# Universal_RGB_to_YPbPR.net
KiCad netlist of a schematic drawn in EAGLE
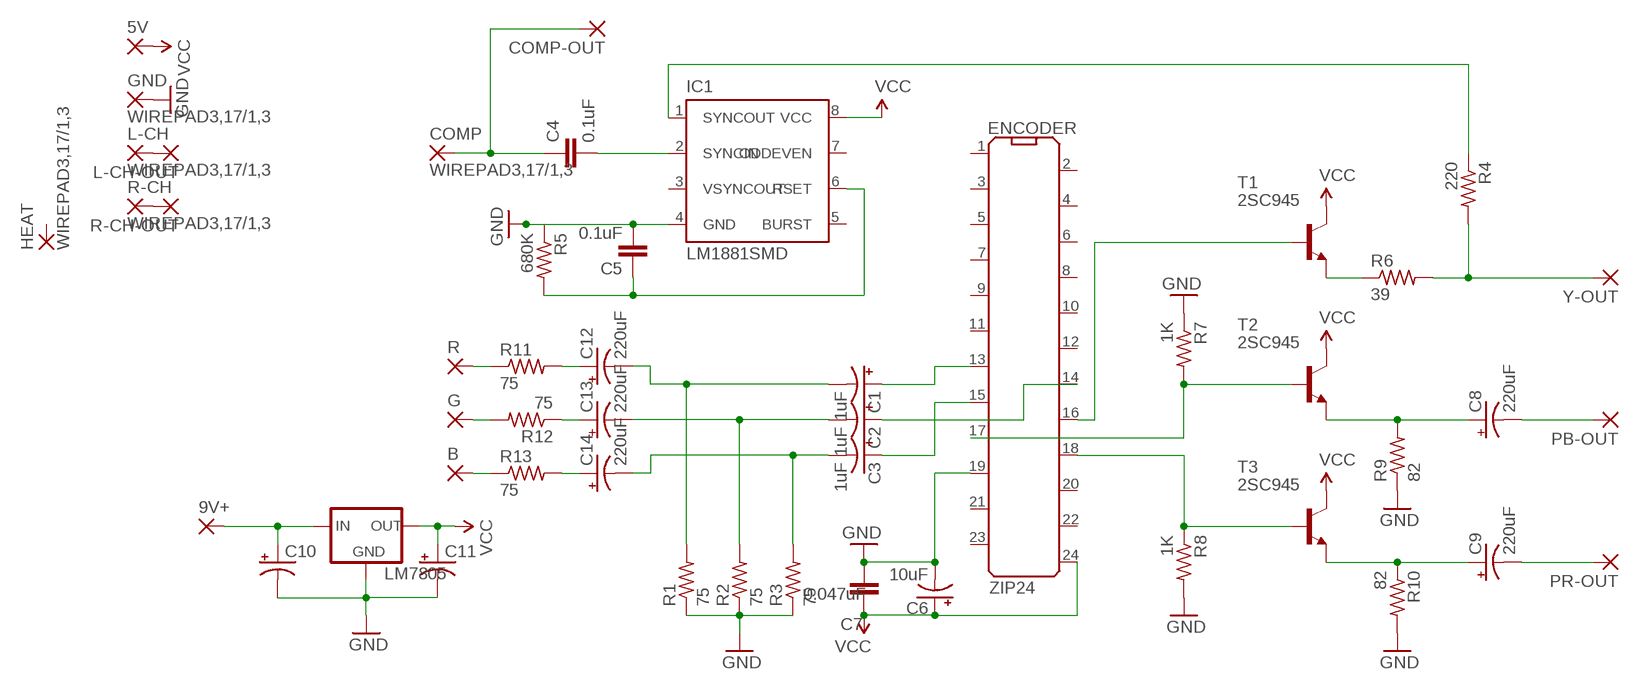
[diagram p0: schematic, sheet 1]

(export (version "E")
  (design (tool "Eeschema 10.0.6"))
  (components
    (comp (ref "5V")
      (value "WIREPAD3,17/1,3")
      (footprint "eagle-import:3,17_1,3")
      (libsource (lib "eagle-import") (part "WIREPAD3,17/1,3"))
    )
    (comp (ref "9V+")
      (value "WIREPAD3,17/1,3")
      (footprint "eagle-import:3,17_1,3")
      (libsource (lib "eagle-import") (part "WIREPAD3,17/1,3"))
    )
    (comp (ref "B")
      (value "WIREPAD3,17/1,3")
      (footprint "eagle-import:3,17_1,3")
      (libsource (lib "eagle-import") (part "WIREPAD3,17/1,3"))
    )
    (comp (ref "C1")
      (value "1uF")
      (footprint "eagle-import:CPOL-RADIAL-10UF-25V")
      (libsource (lib "eagle-import") (part "CAP_POLPTH2"))
    )
    (comp (ref "C2")
      (value "1uF")
      (footprint "eagle-import:CPOL-RADIAL-10UF-25V")
      (libsource (lib "eagle-import") (part "CAP_POLPTH2"))
    )
    (comp (ref "C3")
      (value "1uF")
      (footprint "eagle-import:CPOL-RADIAL-10UF-25V")
      (libsource (lib "eagle-import") (part "CAP_POLPTH2"))
    )
    (comp (ref "C4")
      (value "0.1uF")
      (footprint "eagle-import:C025-024X044")
      (libsource (lib "eagle-import") (part "C-EU025-024X044"))
    )
    (comp (ref "C5")
      (value "0.1uF")
      (footprint "eagle-import:C025-024X044")
      (libsource (lib "eagle-import") (part "C-EU025-024X044"))
    )
    (comp (ref "C6")
      (value "10uF")
      (footprint "eagle-import:CPOL-RADIAL-10UF-25V")
      (libsource (lib "eagle-import") (part "CAP_POLPTH2"))
    )
    (comp (ref "C7")
      (value "0.047uF")
      (footprint "eagle-import:C025-024X044")
      (libsource (lib "eagle-import") (part "C-EU025-024X044"))
    )
    (comp (ref "C8")
      (value "220uF")
      (footprint "eagle-import:CPOL-RADIAL-1000UF-25V")
      (libsource (lib "eagle-import") (part "CAP_POLPTH4"))
    )
    (comp (ref "C9")
      (value "220uF")
      (footprint "eagle-import:CPOL-RADIAL-1000UF-25V")
      (libsource (lib "eagle-import") (part "CAP_POLPTH4"))
    )
    (comp (ref "C10")
      (value "CAP_POLPTH1")
      (footprint "eagle-import:CPOL-RADIAL-100UF-25V")
      (libsource (lib "eagle-import") (part "CAP_POLPTH1"))
    )
    (comp (ref "C11")
      (value "CAP_POLPTH1")
      (footprint "eagle-import:CPOL-RADIAL-100UF-25V")
      (libsource (lib "eagle-import") (part "CAP_POLPTH1"))
    )
    (comp (ref "C12")
      (value "220uF")
      (footprint "eagle-import:CPOL-RADIAL-1000UF-25V")
      (libsource (lib "eagle-import") (part "CAP_POLPTH4"))
    )
    (comp (ref "C13")
      (value "220uF")
      (footprint "eagle-import:CPOL-RADIAL-1000UF-25V")
      (libsource (lib "eagle-import") (part "CAP_POLPTH4"))
    )
    (comp (ref "C14")
      (value "220uF")
      (footprint "eagle-import:CPOL-RADIAL-1000UF-25V")
      (libsource (lib "eagle-import") (part "CAP_POLPTH4"))
    )
    (comp (ref "COMP")
      (value "WIREPAD3,17/1,3")
      (footprint "eagle-import:3,17_1,3")
      (libsource (lib "eagle-import") (part "WIREPAD3,17/1,3"))
    )
    (comp (ref "COMP-OUT")
      (value "WIREPAD3,17/1,3")
      (footprint "eagle-import:3,17_1,3")
      (libsource (lib "eagle-import") (part "WIREPAD3,17/1,3"))
    )
    (comp (ref "ENCODER")
      (value "ZIP24")
      (footprint "eagle-import:ZIP24")
      (libsource (lib "eagle-import") (part "ZIP24"))
    )
    (comp (ref "G")
      (value "WIREPAD3,17/1,3")
      (footprint "eagle-import:3,17_1,3")
      (libsource (lib "eagle-import") (part "WIREPAD3,17/1,3"))
    )
    (comp (ref "GND")
      (value "WIREPAD3,17/1,3")
      (footprint "eagle-import:3,17_1,3")
      (libsource (lib "eagle-import") (part "WIREPAD3,17/1,3"))
    )
    (comp (ref "HEAT")
      (value "WIREPAD3,17/1,3")
      (footprint "eagle-import:3,17_1,3")
      (libsource (lib "eagle-import") (part "WIREPAD3,17/1,3"))
    )
    (comp (ref "IC1")
      (value "LM1881SMD")
      (footprint "eagle-import:SO08")
      (libsource (lib "eagle-import") (part "LM1881SMD"))
    )
    (comp (ref "L-CH")
      (value "WIREPAD3,17/1,3")
      (footprint "eagle-import:3,17_1,3")
      (libsource (lib "eagle-import") (part "WIREPAD3,17/1,3"))
    )
    (comp (ref "L-CH-OUT")
      (value "WIREPAD3,17/1,3")
      (footprint "eagle-import:3,17_1,3")
      (libsource (lib "eagle-import") (part "WIREPAD3,17/1,3"))
    )
    (comp (ref "LM7805")
      (value "V_REG_78XX")
      (footprint "eagle-import:DPAK")
      (libsource (lib "eagle-import") (part "V_REG_78XX"))
    )
    (comp (ref "PB-OUT")
      (value "WIREPAD3,17/1,3")
      (footprint "eagle-import:3,17_1,3")
      (libsource (lib "eagle-import") (part "WIREPAD3,17/1,3"))
    )
    (comp (ref "PR-OUT")
      (value "WIREPAD3,17/1,3")
      (footprint "eagle-import:3,17_1,3")
      (libsource (lib "eagle-import") (part "WIREPAD3,17/1,3"))
    )
    (comp (ref "R")
      (value "WIREPAD3,17/1,3")
      (footprint "eagle-import:3,17_1,3")
      (libsource (lib "eagle-import") (part "WIREPAD3,17/1,3"))
    )
    (comp (ref "R-CH")
      (value "WIREPAD3,17/1,3")
      (footprint "eagle-import:3,17_1,3")
      (libsource (lib "eagle-import") (part "WIREPAD3,17/1,3"))
    )
    (comp (ref "R-CH-OUT")
      (value "WIREPAD3,17/1,3")
      (footprint "eagle-import:3,17_1,3")
      (libsource (lib "eagle-import") (part "WIREPAD3,17/1,3"))
    )
    (comp (ref "R1")
      (value "75")
      (footprint "eagle-import:0207_2V")
      (libsource (lib "eagle-import") (part "R-US_0207/2V"))
    )
    (comp (ref "R2")
      (value "75")
      (footprint "eagle-import:0207_2V")
      (libsource (lib "eagle-import") (part "R-US_0207/2V"))
    )
    (comp (ref "R3")
      (value "75")
      (footprint "eagle-import:0207_2V")
      (libsource (lib "eagle-import") (part "R-US_0207/2V"))
    )
    (comp (ref "R4")
      (value "220")
      (footprint "eagle-import:0207_2V")
      (libsource (lib "eagle-import") (part "R-US_0207/2V"))
    )
    (comp (ref "R5")
      (value "680K")
      (footprint "eagle-import:0207_2V")
      (libsource (lib "eagle-import") (part "R-US_0207/2V"))
    )
    (comp (ref "R6")
      (value "39")
      (footprint "eagle-import:0207_2V")
      (libsource (lib "eagle-import") (part "R-US_0207/2V"))
    )
    (comp (ref "R7")
      (value "1K")
      (footprint "eagle-import:0207_2V")
      (libsource (lib "eagle-import") (part "R-US_0207/2V"))
    )
    (comp (ref "R8")
      (value "1K")
      (footprint "eagle-import:0207_2V")
      (libsource (lib "eagle-import") (part "R-US_0207/2V"))
    )
    (comp (ref "R9")
      (value "82")
      (footprint "eagle-import:0207_2V")
      (libsource (lib "eagle-import") (part "R-US_0207/2V"))
    )
    (comp (ref "R10")
      (value "82")
      (footprint "eagle-import:0207_2V")
      (libsource (lib "eagle-import") (part "R-US_0207/2V"))
    )
    (comp (ref "R11")
      (value "75")
      (footprint "eagle-import:0207_2V")
      (libsource (lib "eagle-import") (part "R-US_0207/2V"))
    )
    (comp (ref "R12")
      (value "75")
      (footprint "eagle-import:0207_2V")
      (libsource (lib "eagle-import") (part "R-US_0207/2V"))
    )
    (comp (ref "R13")
      (value "75")
      (footprint "eagle-import:0207_2V")
      (libsource (lib "eagle-import") (part "R-US_0207/2V"))
    )
    (comp (ref "T1")
      (value "2SC945")
      (footprint "eagle-import:TO92-ECB")
      (libsource (lib "eagle-import") (part "2SC945"))
    )
    (comp (ref "T2")
      (value "2SC945")
      (footprint "eagle-import:TO92-ECB")
      (libsource (lib "eagle-import") (part "2SC945"))
    )
    (comp (ref "T3")
      (value "2SC945")
      (footprint "eagle-import:TO92-ECB")
      (libsource (lib "eagle-import") (part "2SC945"))
    )
    (comp (ref "Y-OUT")
      (value "WIREPAD3,17/1,3")
      (footprint "eagle-import:3,17_1,3")
      (libsource (lib "eagle-import") (part "WIREPAD3,17/1,3"))
    )
  )
  (nets
    (net (code "1") (name "GND") (class "Default")
      (node (ref "C10") (pin "2") (pinfunction "-_2") (pintype "passive"))
      (node (ref "C11") (pin "2") (pinfunction "-_2") (pintype "passive"))
      (node (ref "C5") (pin "2") (pinfunction "2_2") (pintype "passive"))
      (node (ref "C6") (pin "2") (pinfunction "-_2") (pintype "passive"))
      (node (ref "C7") (pin "2") (pinfunction "2_2") (pintype "passive"))
      (node (ref "ENCODER") (pin "19") (pinfunction "GND_19") (pintype "passive"))
      (node (ref "GND") (pin "1") (pinfunction "P_1") (pintype "passive"))
      (node (ref "IC1") (pin "4") (pinfunction "GND_4") (pintype "power_in"))
      (node (ref "LM7805") (pin "4") (pinfunction "GND_4") (pintype "input"))
      (node (ref "R1") (pin "1") (pinfunction "1_1") (pintype "passive"))
      (node (ref "R10") (pin "2") (pinfunction "2_2") (pintype "passive"))
      (node (ref "R2") (pin "1") (pinfunction "1_1") (pintype "passive"))
      (node (ref "R3") (pin "1") (pinfunction "1_1") (pintype "passive"))
      (node (ref "R5") (pin "1") (pinfunction "1_1") (pintype "passive"))
      (node (ref "R7") (pin "1") (pinfunction "1_1") (pintype "passive"))
      (node (ref "R8") (pin "2") (pinfunction "2_2") (pintype "passive"))
      (node (ref "R9") (pin "1") (pinfunction "1_1") (pintype "passive"))
    )
    (net (code "2") (name "Net-(9V+-P)") (class "Default")
      (node (ref "9V+") (pin "1") (pinfunction "P_1") (pintype "passive"))
      (node (ref "C10") (pin "1") (pinfunction "+_1") (pintype "passive"))
      (node (ref "LM7805") (pin "1") (pinfunction "IN_1") (pintype "input"))
    )
    (net (code "3") (name "Net-(B-P)") (class "Default")
      (node (ref "B") (pin "1") (pinfunction "P_1") (pintype "passive"))
      (node (ref "R13") (pin "1") (pinfunction "1_1") (pintype "passive"))
    )
    (net (code "4") (name "Net-(C1-+)") (class "Default")
      (node (ref "C1") (pin "1") (pinfunction "+_1") (pintype "passive"))
      (node (ref "ENCODER") (pin "13") (pinfunction "AR_13") (pintype "passive"))
    )
    (net (code "5") (name "Net-(C1--)") (class "Default")
      (node (ref "C1") (pin "2") (pinfunction "-_2") (pintype "passive"))
      (node (ref "C12") (pin "2") (pinfunction "-_2") (pintype "passive"))
      (node (ref "R1") (pin "2") (pinfunction "2_2") (pintype "passive"))
    )
    (net (code "6") (name "Net-(C2-+)") (class "Default")
      (node (ref "C2") (pin "1") (pinfunction "+_1") (pintype "passive"))
      (node (ref "ENCODER") (pin "14") (pinfunction "AG_14") (pintype "passive"))
    )
    (net (code "7") (name "Net-(C3-+)") (class "Default")
      (node (ref "C3") (pin "1") (pinfunction "+_1") (pintype "passive"))
      (node (ref "ENCODER") (pin "15") (pinfunction "AB_15") (pintype "passive"))
    )
    (net (code "8") (name "Net-(C8-+)") (class "Default")
      (node (ref "C8") (pin "1") (pinfunction "+_1") (pintype "passive"))
      (node (ref "R9") (pin "2") (pinfunction "2_2") (pintype "passive"))
      (node (ref "T2") (pin "E") (pinfunction "E_E") (pintype "passive"))
    )
    (net (code "9") (name "Net-(C8--)") (class "Default")
      (node (ref "C8") (pin "2") (pinfunction "-_2") (pintype "passive"))
      (node (ref "PB-OUT") (pin "1") (pinfunction "P_1") (pintype "passive"))
    )
    (net (code "10") (name "Net-(C9-+)") (class "Default")
      (node (ref "C9") (pin "1") (pinfunction "+_1") (pintype "passive"))
      (node (ref "R10") (pin "1") (pinfunction "1_1") (pintype "passive"))
      (node (ref "T3") (pin "E") (pinfunction "E_E") (pintype "passive"))
    )
    (net (code "11") (name "Net-(C9--)") (class "Default")
      (node (ref "C9") (pin "2") (pinfunction "-_2") (pintype "passive"))
      (node (ref "PR-OUT") (pin "1") (pinfunction "P_1") (pintype "passive"))
    )
    (net (code "12") (name "Net-(C12-+)") (class "Default")
      (node (ref "C12") (pin "1") (pinfunction "+_1") (pintype "passive"))
      (node (ref "R11") (pin "2") (pinfunction "2_2") (pintype "passive"))
    )
    (net (code "13") (name "Net-(C13-+)") (class "Default")
      (node (ref "C13") (pin "1") (pinfunction "+_1") (pintype "passive"))
      (node (ref "R12") (pin "1") (pinfunction "1_1") (pintype "passive"))
    )
    (net (code "14") (name "Net-(C13--)") (class "Default")
      (node (ref "C13") (pin "2") (pinfunction "-_2") (pintype "passive"))
      (node (ref "C2") (pin "2") (pinfunction "-_2") (pintype "passive"))
      (node (ref "R2") (pin "2") (pinfunction "2_2") (pintype "passive"))
    )
    (net (code "15") (name "Net-(C14-+)") (class "Default")
      (node (ref "C14") (pin "1") (pinfunction "+_1") (pintype "passive"))
      (node (ref "R13") (pin "2") (pinfunction "2_2") (pintype "passive"))
    )
    (net (code "16") (name "Net-(C14--)") (class "Default")
      (node (ref "C14") (pin "2") (pinfunction "-_2") (pintype "passive"))
      (node (ref "C3") (pin "2") (pinfunction "-_2") (pintype "passive"))
      (node (ref "R3") (pin "2") (pinfunction "2_2") (pintype "passive"))
    )
    (net (code "17") (name "Net-(COMP-OUT-P)") (class "Default")
      (node (ref "C4") (pin "1") (pinfunction "1_1") (pintype "passive"))
      (node (ref "COMP") (pin "1") (pinfunction "P_1") (pintype "passive"))
      (node (ref "COMP-OUT") (pin "1") (pinfunction "P_1") (pintype "passive"))
    )
    (net (code "18") (name "Net-(ENCODER-B-Y-OUT)") (class "Default")
      (node (ref "ENCODER") (pin "17") (pinfunction "B-Y-OUT_17") (pintype "passive"))
      (node (ref "R7") (pin "2") (pinfunction "2_2") (pintype "passive"))
      (node (ref "T2") (pin "B") (pinfunction "B_B") (pintype "passive"))
    )
    (net (code "19") (name "Net-(ENCODER-R-Y-OUT)") (class "Default")
      (node (ref "ENCODER") (pin "18") (pinfunction "R-Y-OUT_18") (pintype "passive"))
      (node (ref "R8") (pin "1") (pinfunction "1_1") (pintype "passive"))
      (node (ref "T3") (pin "B") (pinfunction "B_B") (pintype "passive"))
    )
    (net (code "20") (name "Net-(ENCODER-Y-OUT)") (class "Default")
      (node (ref "ENCODER") (pin "16") (pinfunction "Y-OUT_16") (pintype "passive"))
      (node (ref "T1") (pin "B") (pinfunction "B_B") (pintype "passive"))
    )
    (net (code "21") (name "Net-(G-P)") (class "Default")
      (node (ref "G") (pin "1") (pinfunction "P_1") (pintype "passive"))
      (node (ref "R12") (pin "2") (pinfunction "2_2") (pintype "passive"))
    )
    (net (code "22") (name "Net-(IC1-RSET)") (class "Default")
      (node (ref "C5") (pin "1") (pinfunction "1_1") (pintype "passive"))
      (node (ref "IC1") (pin "6") (pinfunction "RSET_6") (pintype "output"))
      (node (ref "R5") (pin "2") (pinfunction "2_2") (pintype "passive"))
    )
    (net (code "23") (name "Net-(IC1-SYNCIN)") (class "Default")
      (node (ref "C4") (pin "2") (pinfunction "2_2") (pintype "passive"))
      (node (ref "IC1") (pin "2") (pinfunction "SYNCIN_2") (pintype "input"))
    )
    (net (code "24") (name "Net-(IC1-SYNCOUT)") (class "Default")
      (node (ref "IC1") (pin "1") (pinfunction "SYNCOUT_1") (pintype "output"))
      (node (ref "R4") (pin "1") (pinfunction "1_1") (pintype "passive"))
    )
    (net (code "25") (name "Net-(L-CH-OUT-P)") (class "Default")
      (node (ref "L-CH") (pin "1") (pinfunction "P_1") (pintype "passive"))
      (node (ref "L-CH-OUT") (pin "1") (pinfunction "P_1") (pintype "passive"))
    )
    (net (code "26") (name "Net-(R-CH-OUT-P)") (class "Default")
      (node (ref "R-CH") (pin "1") (pinfunction "P_1") (pintype "passive"))
      (node (ref "R-CH-OUT") (pin "1") (pinfunction "P_1") (pintype "passive"))
    )
    (net (code "27") (name "Net-(R-P)") (class "Default")
      (node (ref "R") (pin "1") (pinfunction "P_1") (pintype "passive"))
      (node (ref "R11") (pin "1") (pinfunction "1_1") (pintype "passive"))
    )
    (net (code "28") (name "Net-(R6-Pad1)") (class "Default")
      (node (ref "R6") (pin "1") (pinfunction "1_1") (pintype "passive"))
      (node (ref "T1") (pin "E") (pinfunction "E_E") (pintype "passive"))
    )
    (net (code "29") (name "Net-(Y-OUT-P)") (class "Default")
      (node (ref "R4") (pin "2") (pinfunction "2_2") (pintype "passive"))
      (node (ref "R6") (pin "2") (pinfunction "2_2") (pintype "passive"))
      (node (ref "Y-OUT") (pin "1") (pinfunction "P_1") (pintype "passive"))
    )
    (net (code "30") (name "VCC") (class "Default")
      (node (ref "5V") (pin "1") (pinfunction "P_1") (pintype "passive"))
      (node (ref "C11") (pin "1") (pinfunction "+_1") (pintype "passive"))
      (node (ref "C6") (pin "1") (pinfunction "+_1") (pintype "passive"))
      (node (ref "C7") (pin "1") (pinfunction "1_1") (pintype "passive"))
      (node (ref "ENCODER") (pin "24") (pinfunction "VCC_24") (pintype "passive"))
      (node (ref "IC1") (pin "8") (pinfunction "VCC_8") (pintype "power_in"))
      (node (ref "LM7805") (pin "3") (pinfunction "OUT_3") (pintype "output"))
      (node (ref "T1") (pin "C") (pinfunction "C_C") (pintype "passive"))
      (node (ref "T2") (pin "C") (pinfunction "C_C") (pintype "passive"))
      (node (ref "T3") (pin "C") (pinfunction "C_C") (pintype "passive"))
    )
    (net (code "31") (name "unconnected-(ENCODER-APC-PHASE-ADJ-Pad11)") (class "Default")
      (node (ref "ENCODER") (pin "11") (pinfunction "APC-PHASE-ADJ_11") (pintype "passive"))
    )
    (net (code "32") (name "unconnected-(ENCODER-B-Y-IN-Pad4)") (class "Default")
      (node (ref "ENCODER") (pin "4") (pinfunction "B-Y-IN_4") (pintype "passive"))
    )
    (net (code "33") (name "unconnected-(ENCODER-BFP-IN-Pad10)") (class "Default")
      (node (ref "ENCODER") (pin "10") (pinfunction "BFP-IN_10") (pintype "passive"))
    )
    (net (code "34") (name "unconnected-(ENCODER-BURST-LV-ADJ-Pad6)") (class "Default")
      (node (ref "ENCODER") (pin "6") (pinfunction "BURST-LV-ADJ_6") (pintype "passive"))
    )
    (net (code "35") (name "unconnected-(ENCODER-HDP-IN-Pad22)") (class "Default")
      (node (ref "ENCODER") (pin "22") (pinfunction "HDP-IN_22") (pintype "passive"))
    )
    (net (code "36") (name "unconnected-(ENCODER-PCP-IN-Pad21)") (class "Default")
      (node (ref "ENCODER") (pin "21") (pinfunction "PCP-IN_21") (pintype "passive"))
    )
    (net (code "37") (name "unconnected-(ENCODER-PD-Pad12)") (class "Default")
      (node (ref "ENCODER") (pin "12") (pinfunction "PD_12") (pintype "passive"))
    )
    (net (code "38") (name "unconnected-(ENCODER-R-Y-IN-Pad5)") (class "Default")
      (node (ref "ENCODER") (pin "5") (pinfunction "R-Y-IN_5") (pintype "passive"))
    )
    (net (code "39") (name "unconnected-(ENCODER-SYNC-IN-Pad2)") (class "Default")
      (node (ref "ENCODER") (pin "2") (pinfunction "SYNC-IN_2") (pintype "passive"))
    )
    (net (code "40") (name "unconnected-(ENCODER-VA-Pad9)") (class "Default")
      (node (ref "ENCODER") (pin "9") (pinfunction "VA_9") (pintype "passive"))
    )
    (net (code "41") (name "unconnected-(ENCODER-VB-Pad8)") (class "Default")
      (node (ref "ENCODER") (pin "8") (pinfunction "VB_8") (pintype "passive"))
    )
    (net (code "42") (name "unconnected-(ENCODER-VC-Pad7)") (class "Default")
      (node (ref "ENCODER") (pin "7") (pinfunction "VC_7") (pintype "passive"))
    )
    (net (code "43") (name "unconnected-(ENCODER-VID-IN-Pad20)") (class "Default")
      (node (ref "ENCODER") (pin "20") (pinfunction "VID-IN_20") (pintype "passive"))
    )
    (net (code "44") (name "unconnected-(ENCODER-VID-OUT-Pad1)") (class "Default")
      (node (ref "ENCODER") (pin "1") (pinfunction "VID-OUT_1") (pintype "passive"))
    )
    (net (code "45") (name "unconnected-(ENCODER-Y-IN-Pad3)") (class "Default")
      (node (ref "ENCODER") (pin "3") (pinfunction "Y-IN_3") (pintype "passive"))
    )
    (net (code "46") (name "unconnected-(ENCODER-YSP-IN-Pad23)") (class "Default")
      (node (ref "ENCODER") (pin "23") (pinfunction "YSP-IN_23") (pintype "passive"))
    )
    (net (code "47") (name "unconnected-(HEAT-P-Pad1)") (class "Default")
      (node (ref "HEAT") (pin "1") (pinfunction "P_1") (pintype "passive"))
    )
    (net (code "48") (name "unconnected-(IC1-BURST-Pad5)") (class "Default")
      (node (ref "IC1") (pin "5") (pinfunction "BURST_5") (pintype "output"))
    )
    (net (code "49") (name "unconnected-(IC1-ODDEVEN-Pad7)") (class "Default")
      (node (ref "IC1") (pin "7") (pinfunction "ODDEVEN_7") (pintype "output"))
    )
    (net (code "50") (name "unconnected-(IC1-VSYNCOUT-Pad3)") (class "Default")
      (node (ref "IC1") (pin "3") (pinfunction "VSYNCOUT_3") (pintype "output"))
    )
  )
)
